# schematic.net
KiCad netlist of a schematic drawn in EAGLE
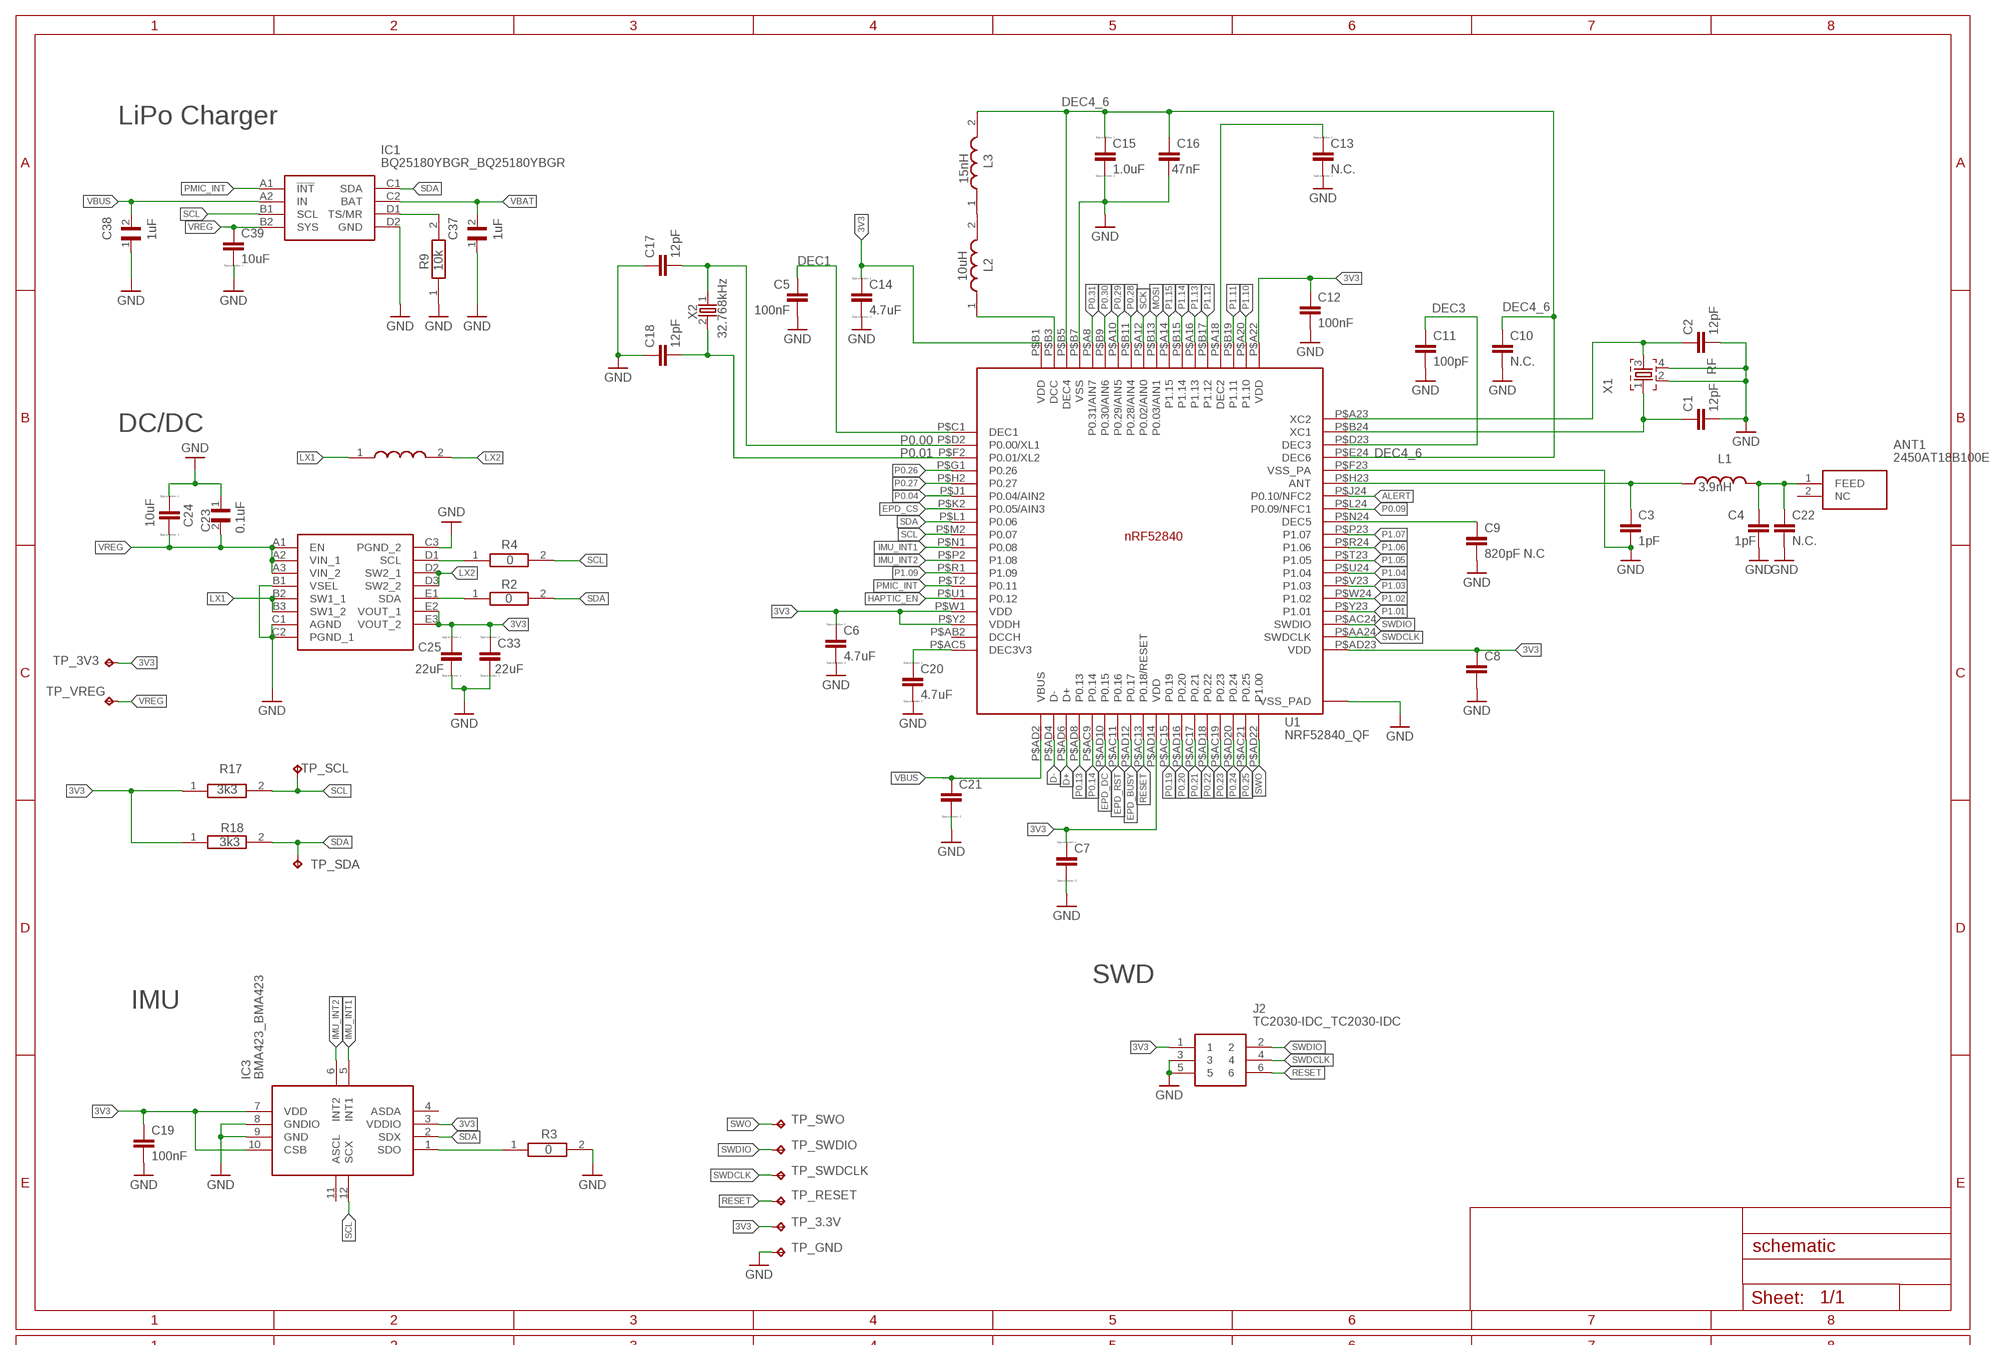
[diagram p0: schematic, sheet 1, part 1 of 2]
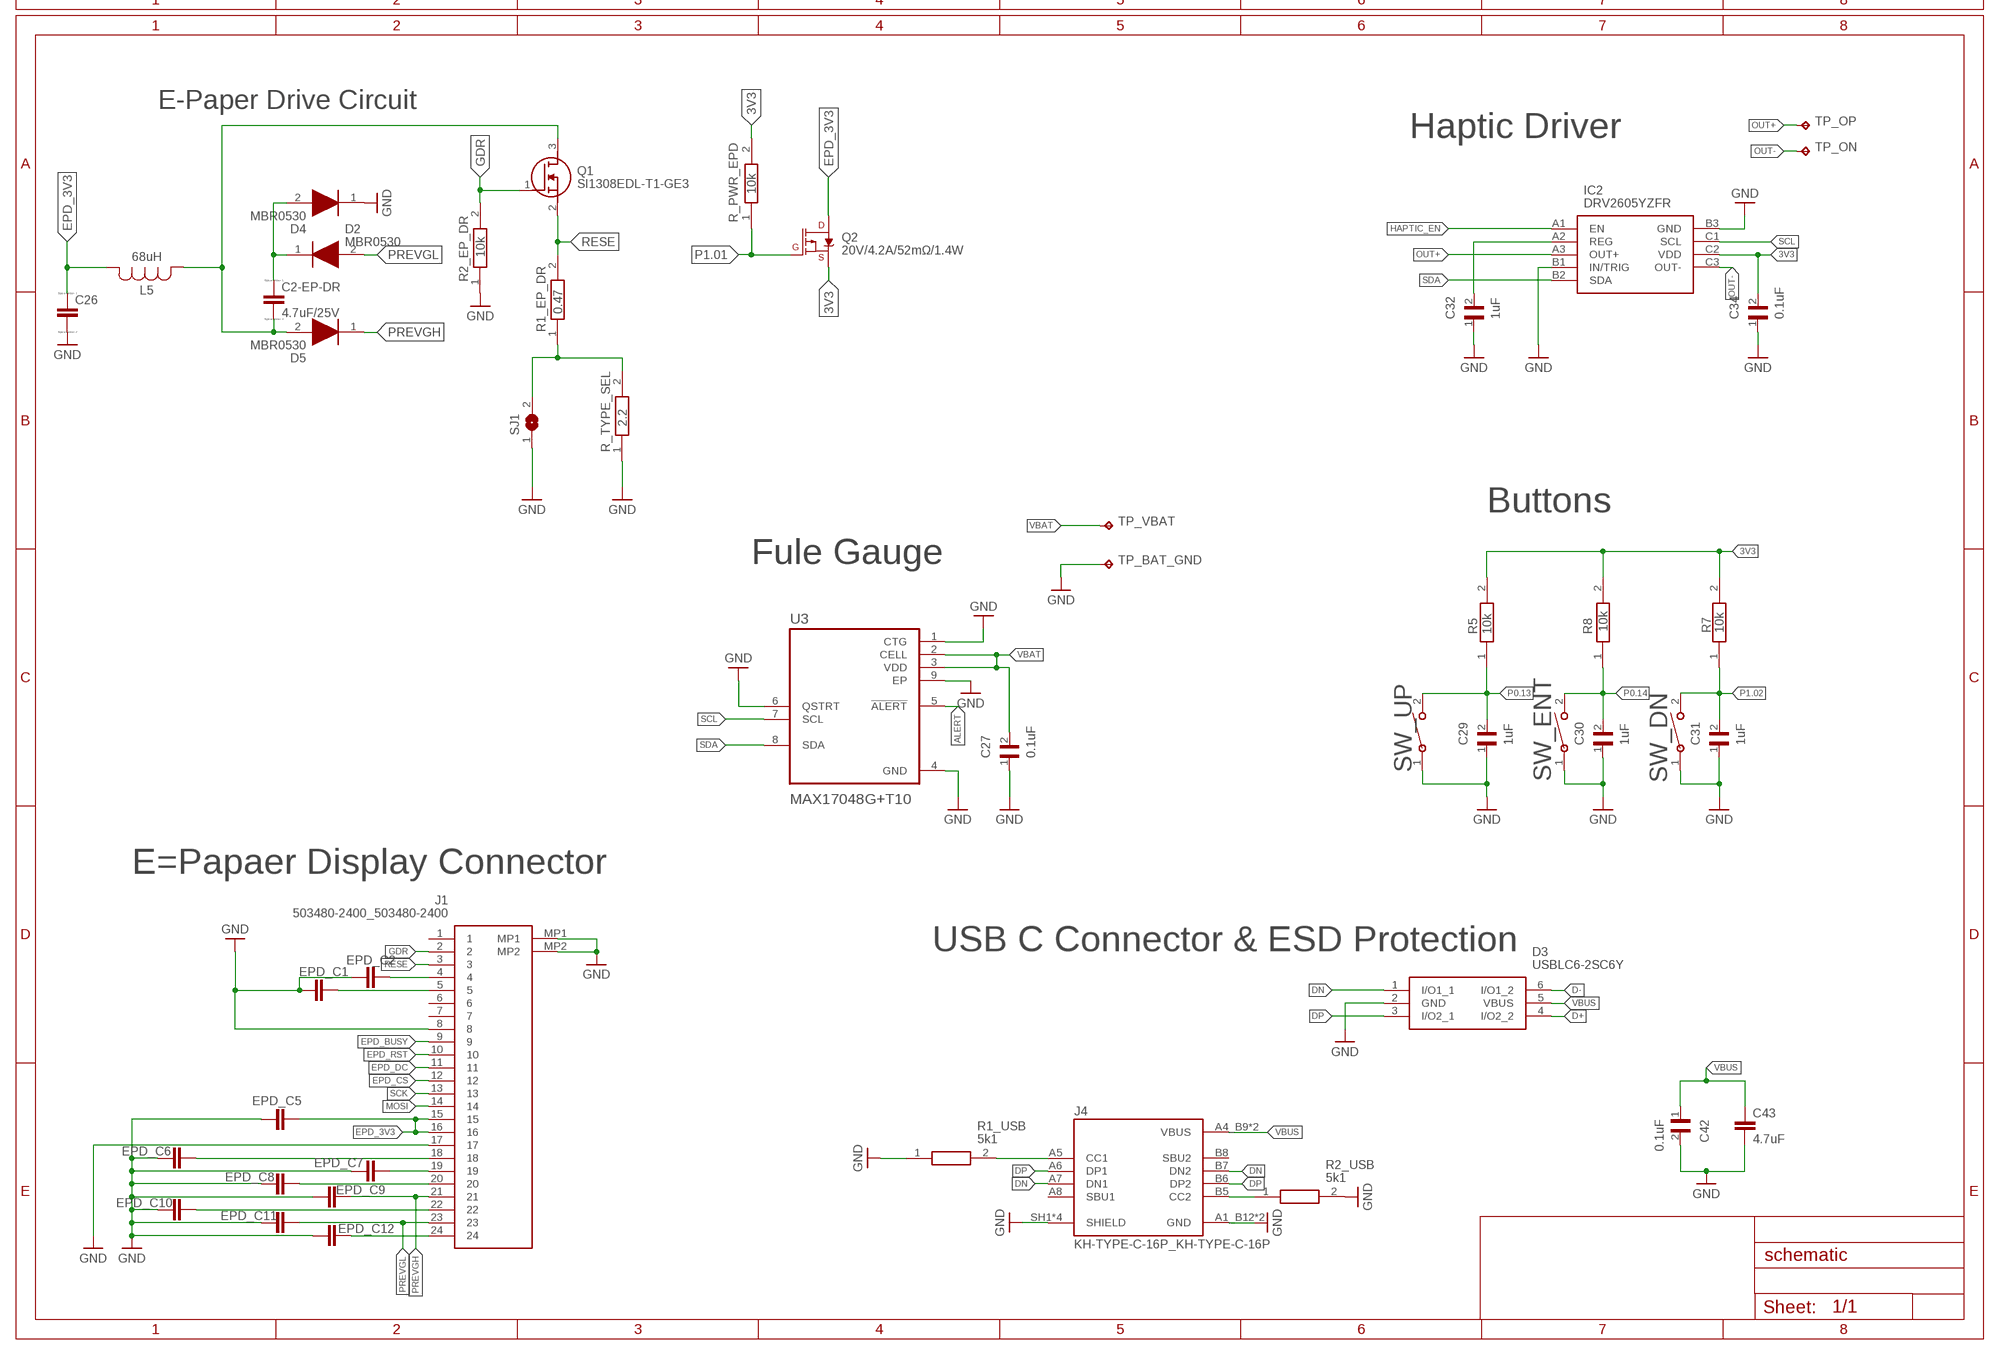
[diagram p1: schematic, sheet 1, part 2 of 2]

(export (version "E")
  (design (tool "Eeschema 10.0.6"))
  (components
    (comp (ref "ANT1")
      (value "2450AT18B100E")
      (footprint "eagle-import:2450AT18B100E_ANTC3216X140N")
      (fields (field (name "MOUSER_PART_NUMBER") "609-2450AT18B100E"))
      (libsource (lib "eagle-import") (part "2450AT18B100E_2450AT18B100E"))
    )
    (comp (ref "C1")
      (value "12pF")
      (footprint "eagle-import:NORDIC_NRF_3_RESC0201_L")
      (libsource (lib "eagle-import") (part "NORDIC_NRF_3_CAPACITOR_0201_L"))
    )
    (comp (ref "C2")
      (value "12pF")
      (footprint "eagle-import:NORDIC_NRF_3_RESC0201_L")
      (libsource (lib "eagle-import") (part "NORDIC_NRF_3_CAPACITOR_0201_L"))
    )
    (comp (ref "C2-EP-DR")
      (value "4.7uF/25V")
      (footprint "eagle-import:ESP32_C6_LIBRARY_1_ESP32_WROVER_EAGLE-LTSPICE_C0402")
      (libsource (lib "eagle-import") (part "ESP32_C6_LIBRARY_1_ESP32_WROVER_EAGLE-LTSPICE_CC0402"))
    )
    (comp (ref "C3")
      (value "1pF")
      (footprint "eagle-import:NORDIC_NRF_3_RESC0201_L")
      (libsource (lib "eagle-import") (part "NORDIC_NRF_3_CAPACITOR_0201_L"))
    )
    (comp (ref "C4")
      (value "1pF")
      (footprint "eagle-import:NORDIC_NRF_3_RESC0201_L")
      (libsource (lib "eagle-import") (part "NORDIC_NRF_3_CAPACITOR_0201_L"))
    )
    (comp (ref "C5")
      (value "100nF")
      (footprint "eagle-import:NORDIC_NRF_3_RESC0201_L")
      (libsource (lib "eagle-import") (part "NORDIC_NRF_3_CAPACITOR_0201_L"))
    )
    (comp (ref "C6")
      (value "4.7uF")
      (footprint "eagle-import:ESP32_C6_LIBRARY_1_ESP32_WROVER_EAGLE-LTSPICE_C0402")
      (libsource (lib "eagle-import") (part "ESP32_C6_LIBRARY_1_ESP32_WROVER_EAGLE-LTSPICE_CC0402"))
    )
    (comp (ref "C7")
      (value "ESP32_C6_LIBRARY_1_ESP32_WROVER_EAGLE-LTSPICE_CC0402")
      (footprint "eagle-import:ESP32_C6_LIBRARY_1_ESP32_WROVER_EAGLE-LTSPICE_C0402")
      (libsource (lib "eagle-import") (part "ESP32_C6_LIBRARY_1_ESP32_WROVER_EAGLE-LTSPICE_CC0402"))
    )
    (comp (ref "C8")
      (value "NORDIC_NRF_3_CAPACITOR_0201_L")
      (footprint "eagle-import:NORDIC_NRF_3_RESC0201_L")
      (libsource (lib "eagle-import") (part "NORDIC_NRF_3_CAPACITOR_0201_L"))
    )
    (comp (ref "C9")
      (value "820pF N.C")
      (footprint "eagle-import:NORDIC_NRF_3_RESC0201_L")
      (libsource (lib "eagle-import") (part "NORDIC_NRF_3_CAPACITOR_0201_L"))
    )
    (comp (ref "C10")
      (value "N.C.")
      (footprint "eagle-import:NORDIC_NRF_3_RESC0201_L")
      (libsource (lib "eagle-import") (part "NORDIC_NRF_3_CAPACITOR_0201_L"))
    )
    (comp (ref "C11")
      (value "100pF")
      (footprint "eagle-import:NORDIC_NRF_3_RESC0201_L")
      (libsource (lib "eagle-import") (part "NORDIC_NRF_3_CAPACITOR_0201_L"))
    )
    (comp (ref "C12")
      (value "100nF")
      (footprint "eagle-import:NORDIC_NRF_3_RESC0201_L")
      (libsource (lib "eagle-import") (part "NORDIC_NRF_3_CAPACITOR_0201_L"))
    )
    (comp (ref "C13")
      (value "N.C.")
      (footprint "eagle-import:ESP32_C6_LIBRARY_1_ESP32_WROVER_EAGLE-LTSPICE_C0402")
      (libsource (lib "eagle-import") (part "ESP32_C6_LIBRARY_1_ESP32_WROVER_EAGLE-LTSPICE_CC0402"))
    )
    (comp (ref "C14")
      (value "4.7uF")
      (footprint "eagle-import:ESP32_C6_LIBRARY_1_ESP32_WROVER_EAGLE-LTSPICE_C0402")
      (libsource (lib "eagle-import") (part "ESP32_C6_LIBRARY_1_ESP32_WROVER_EAGLE-LTSPICE_CC0402"))
    )
    (comp (ref "C15")
      (value "1.0uF")
      (footprint "eagle-import:ESP32_C6_LIBRARY_1_ESP32_WROVER_EAGLE-LTSPICE_C0402")
      (libsource (lib "eagle-import") (part "ESP32_C6_LIBRARY_1_ESP32_WROVER_EAGLE-LTSPICE_CC0402"))
    )
    (comp (ref "C16")
      (value "47nF")
      (footprint "eagle-import:NORDIC_NRF_3_RESC0201_L")
      (libsource (lib "eagle-import") (part "NORDIC_NRF_3_CAPACITOR_0201_L"))
    )
    (comp (ref "C17")
      (value "12pF")
      (footprint "eagle-import:NORDIC_NRF_3_RESC0201_L")
      (libsource (lib "eagle-import") (part "NORDIC_NRF_3_CAPACITOR_0201_L"))
    )
    (comp (ref "C18")
      (value "12pF")
      (footprint "eagle-import:NORDIC_NRF_3_RESC0201_L")
      (libsource (lib "eagle-import") (part "NORDIC_NRF_3_CAPACITOR_0201_L"))
    )
    (comp (ref "C19")
      (value "100nF")
      (footprint "eagle-import:NORDIC_NRF_3_RESC0201_L")
      (libsource (lib "eagle-import") (part "NORDIC_NRF_3_CAPACITOR_0201_L"))
    )
    (comp (ref "C20")
      (value "4.7uF")
      (footprint "eagle-import:ESP32_C6_LIBRARY_1_ESP32_WROVER_EAGLE-LTSPICE_C0402")
      (libsource (lib "eagle-import") (part "ESP32_C6_LIBRARY_1_ESP32_WROVER_EAGLE-LTSPICE_CC0402"))
    )
    (comp (ref "C21")
      (value "ESP32_C6_LIBRARY_1_ESP32_WROVER_EAGLE-LTSPICE_CC0402")
      (footprint "eagle-import:ESP32_C6_LIBRARY_1_ESP32_WROVER_EAGLE-LTSPICE_C0402")
      (libsource (lib "eagle-import") (part "ESP32_C6_LIBRARY_1_ESP32_WROVER_EAGLE-LTSPICE_CC0402"))
    )
    (comp (ref "C22")
      (value "N.C.")
      (footprint "eagle-import:NORDIC_NRF_3_RESC0201_L")
      (libsource (lib "eagle-import") (part "NORDIC_NRF_3_CAPACITOR_0201_L"))
    )
    (comp (ref "C23")
      (value "0.1uF")
      (footprint "eagle-import:GRM011R60J152KE01L_2_CAPC0201X13N")
      (fields (field (name "MF") "Murata") (field (name "MP") "GRM011R60J152KE01L"))
      (libsource (lib "eagle-import") (part "GRM011R60J152KE01L_2_GRM011R60J152KE01L"))
    )
    (comp (ref "C24")
      (value "10uF")
      (footprint "eagle-import:ESP32_C6_LIBRARY_1_ESP32_WROVER_EAGLE-LTSPICE_C0402")
      (libsource (lib "eagle-import") (part "ESP32_C6_LIBRARY_1_ESP32_WROVER_EAGLE-LTSPICE_CC0402"))
    )
    (comp (ref "C25")
      (value "22uF")
      (footprint "eagle-import:ESP32_C6_LIBRARY_1_ESP32_WROVER_EAGLE-LTSPICE_C0402")
      (libsource (lib "eagle-import") (part "ESP32_C6_LIBRARY_1_ESP32_WROVER_EAGLE-LTSPICE_CC0402"))
    )
    (comp (ref "C26")
      (value "ESP32_C6_LIBRARY_1_ESP32_WROVER_EAGLE-LTSPICE_CC0402")
      (footprint "eagle-import:ESP32_C6_LIBRARY_1_ESP32_WROVER_EAGLE-LTSPICE_C0402")
      (libsource (lib "eagle-import") (part "ESP32_C6_LIBRARY_1_ESP32_WROVER_EAGLE-LTSPICE_CC0402"))
    )
    (comp (ref "C27")
      (value "0.1uF")
      (footprint "eagle-import:GRM011R60J152KE01L_2_CAPC0201X13N")
      (fields (field (name "MF") "Murata") (field (name "MP") "GRM011R60J152KE01L"))
      (libsource (lib "eagle-import") (part "GRM011R60J152KE01L_2_GRM011R60J152KE01L"))
    )
    (comp (ref "C29")
      (value "1uF")
      (footprint "eagle-import:GRM011R60J152KE01L_2_CAPC0201X13N")
      (fields (field (name "MF") "Murata") (field (name "MP") "GRM011R60J152KE01L"))
      (libsource (lib "eagle-import") (part "GRM011R60J152KE01L_2_GRM011R60J152KE01L"))
    )
    (comp (ref "C30")
      (value "1uF")
      (footprint "eagle-import:GRM011R60J152KE01L_2_CAPC0201X13N")
      (fields (field (name "MF") "Murata") (field (name "MP") "GRM011R60J152KE01L"))
      (libsource (lib "eagle-import") (part "GRM011R60J152KE01L_2_GRM011R60J152KE01L"))
    )
    (comp (ref "C31")
      (value "1uF")
      (footprint "eagle-import:GRM011R60J152KE01L_2_CAPC0201X13N")
      (fields (field (name "MF") "Murata") (field (name "MP") "GRM011R60J152KE01L"))
      (libsource (lib "eagle-import") (part "GRM011R60J152KE01L_2_GRM011R60J152KE01L"))
    )
    (comp (ref "C32")
      (value "1uF")
      (footprint "eagle-import:GRM011R60J152KE01L_2_CAPC0201X13N")
      (fields (field (name "MF") "Murata") (field (name "MP") "GRM011R60J152KE01L"))
      (libsource (lib "eagle-import") (part "GRM011R60J152KE01L_2_GRM011R60J152KE01L"))
    )
    (comp (ref "C33")
      (value "22uF")
      (footprint "eagle-import:ESP32_C6_LIBRARY_1_ESP32_WROVER_EAGLE-LTSPICE_C0402")
      (libsource (lib "eagle-import") (part "ESP32_C6_LIBRARY_1_ESP32_WROVER_EAGLE-LTSPICE_CC0402"))
    )
    (comp (ref "C34")
      (value "0.1uF")
      (footprint "eagle-import:GRM011R60J152KE01L_2_CAPC0201X13N")
      (fields (field (name "MF") "Murata") (field (name "MP") "GRM011R60J152KE01L"))
      (libsource (lib "eagle-import") (part "GRM011R60J152KE01L_2_GRM011R60J152KE01L"))
    )
    (comp (ref "C37")
      (value "1uF")
      (footprint "eagle-import:GRM011R60J152KE01L_2_CAPC0201X13N")
      (fields (field (name "MF") "Murata") (field (name "MP") "GRM011R60J152KE01L"))
      (libsource (lib "eagle-import") (part "GRM011R60J152KE01L_2_GRM011R60J152KE01L"))
    )
    (comp (ref "C38")
      (value "1uF")
      (footprint "eagle-import:GRM011R60J152KE01L_2_CAPC0201X13N")
      (fields (field (name "MF") "Murata") (field (name "MP") "GRM011R60J152KE01L"))
      (libsource (lib "eagle-import") (part "GRM011R60J152KE01L_2_GRM011R60J152KE01L"))
    )
    (comp (ref "C39")
      (value "10uF")
      (footprint "eagle-import:ESP32_C6_LIBRARY_1_ESP32_WROVER_EAGLE-LTSPICE_C0402")
      (libsource (lib "eagle-import") (part "ESP32_C6_LIBRARY_1_ESP32_WROVER_EAGLE-LTSPICE_CC0402"))
    )
    (comp (ref "C42")
      (value "0.1uF")
      (footprint "eagle-import:GRM011R60J152KE01L_2_CAPC0201X13N")
      (fields (field (name "MF") "Murata") (field (name "MP") "GRM011R60J152KE01L"))
      (libsource (lib "eagle-import") (part "GRM011R60J152KE01L_2_GRM011R60J152KE01L"))
    )
    (comp (ref "C43")
      (value "4.7uF")
      (footprint "eagle-import:NORDIC_NRF_3_RESC0402_L")
      (libsource (lib "eagle-import") (part "NORDIC_NRF_3_CAPACITOR_0402_L"))
    )
    (comp (ref "D2")
      (value "MBR0530")
      (footprint "eagle-import:ESP32_C6_LIBRARY_5_SOD3716X135N")
      (fields (field (name "MF") "ON Semiconductor"))
      (libsource (lib "eagle-import") (part "ESP32_C6_LIBRARY_5_MBR0530"))
    )
    (comp (ref "D3")
      (value "USBLC6-2SC6Y")
      (footprint "eagle-import:ESP32_C6_LIBRARY_3_SOT95P280X145-6N")
      (fields (field (name "MF") "STMicroelectronics"))
      (libsource (lib "eagle-import") (part "ESP32_C6_LIBRARY_3_USBLC6-2SC6Y"))
    )
    (comp (ref "D4")
      (value "MBR0530")
      (footprint "eagle-import:ESP32_C6_LIBRARY_5_SOD3716X135N")
      (fields (field (name "MF") "ON Semiconductor"))
      (libsource (lib "eagle-import") (part "ESP32_C6_LIBRARY_5_MBR0530"))
    )
    (comp (ref "D5")
      (value "MBR0530")
      (footprint "eagle-import:ESP32_C6_LIBRARY_5_SOD3716X135N")
      (fields (field (name "MF") "ON Semiconductor"))
      (libsource (lib "eagle-import") (part "ESP32_C6_LIBRARY_5_MBR0530"))
    )
    (comp (ref "EPD_C1")
      (value "NORDIC_NRF_3_CAPACITOR_0402_L")
      (footprint "eagle-import:NORDIC_NRF_3_RESC0402_L")
      (libsource (lib "eagle-import") (part "NORDIC_NRF_3_CAPACITOR_0402_L"))
    )
    (comp (ref "EPD_C2")
      (value "NORDIC_NRF_3_CAPACITOR_0402_L")
      (footprint "eagle-import:NORDIC_NRF_3_RESC0402_L")
      (libsource (lib "eagle-import") (part "NORDIC_NRF_3_CAPACITOR_0402_L"))
    )
    (comp (ref "EPD_C5")
      (value "NORDIC_NRF_3_CAPACITOR_0402_L")
      (footprint "eagle-import:NORDIC_NRF_3_RESC0402_L")
      (libsource (lib "eagle-import") (part "NORDIC_NRF_3_CAPACITOR_0402_L"))
    )
    (comp (ref "EPD_C6")
      (value "NORDIC_NRF_3_CAPACITOR_0402_L")
      (footprint "eagle-import:NORDIC_NRF_3_RESC0402_L")
      (libsource (lib "eagle-import") (part "NORDIC_NRF_3_CAPACITOR_0402_L"))
    )
    (comp (ref "EPD_C7")
      (value "NORDIC_NRF_3_CAPACITOR_0402_L")
      (footprint "eagle-import:NORDIC_NRF_3_RESC0402_L")
      (libsource (lib "eagle-import") (part "NORDIC_NRF_3_CAPACITOR_0402_L"))
    )
    (comp (ref "EPD_C8")
      (value "NORDIC_NRF_3_CAPACITOR_0402_L")
      (footprint "eagle-import:NORDIC_NRF_3_RESC0402_L")
      (libsource (lib "eagle-import") (part "NORDIC_NRF_3_CAPACITOR_0402_L"))
    )
    (comp (ref "EPD_C9")
      (value "NORDIC_NRF_3_CAPACITOR_0402_L")
      (footprint "eagle-import:NORDIC_NRF_3_RESC0402_L")
      (libsource (lib "eagle-import") (part "NORDIC_NRF_3_CAPACITOR_0402_L"))
    )
    (comp (ref "EPD_C10")
      (value "NORDIC_NRF_3_CAPACITOR_0402_L")
      (footprint "eagle-import:NORDIC_NRF_3_RESC0402_L")
      (libsource (lib "eagle-import") (part "NORDIC_NRF_3_CAPACITOR_0402_L"))
    )
    (comp (ref "EPD_C11")
      (value "NORDIC_NRF_3_CAPACITOR_0402_L")
      (footprint "eagle-import:NORDIC_NRF_3_RESC0402_L")
      (libsource (lib "eagle-import") (part "NORDIC_NRF_3_CAPACITOR_0402_L"))
    )
    (comp (ref "EPD_C12")
      (value "NORDIC_NRF_3_CAPACITOR_0402_L")
      (footprint "eagle-import:NORDIC_NRF_3_RESC0402_L")
      (libsource (lib "eagle-import") (part "NORDIC_NRF_3_CAPACITOR_0402_L"))
    )
    (comp (ref "IC1")
      (value "BQ25180YBGR_BQ25180YBGR")
      (footprint "eagle-import:BQ25180YBGR_BGA8C40P2X4_100X155X50")
      (fields
        (field (name "ARROW_PART_NUMBER") "BQ25180YBGR")
        (field (name "MOUSER_PART_NUMBER") "595-BQ25180YBGR")
      )
      (libsource (lib "eagle-import") (part "BQ25180YBGR_BQ25180YBGR"))
    )
    (comp (ref "IC2")
      (value "DRV2605YZFR")
      (footprint "eagle-import:DRV2605YZFR_BGA9C50P3X3_144X144X62")
      (libsource (lib "eagle-import") (part "DRV2605YZFR_DRV2605YZFR"))
    )
    (comp (ref "IC3")
      (value "BMA423_BMA423")
      (footprint "eagle-import:BMA423_BMA423")
      (fields (field (name "ARROW_PART_NUMBER") "BMA423") (field (name "MOUSER_PART_NUMBER") "262-BMA423"))
      (libsource (lib "eagle-import") (part "BMA423_BMA423"))
    )
    (comp (ref "IC9")
      (value "RT6160AWSC_RT6160AWSC")
      (footprint "eagle-import:RT6160AWSC_BGA15C40P3X5_140X230X60")
      (fields
        (field (name "MANUFACTURER_PART_NUMBER") "RT6160AWSC")
        (field (name "MOUSER_PART_NUMBER") "835-RT6160AWSC")
      )
      (libsource (lib "eagle-import") (part "RT6160AWSC_RT6160AWSC"))
    )
    (comp (ref "J1")
      (value "503480-2400_503480-2400")
      (footprint "eagle-import:503480-2400_5034802400")
      (fields
        (field (name "MANUFACTURER_PART_NUMBER") "503480-2400")
        (field (name "MOUSER_PART_NUMBER") "538-503480-2400")
      )
      (libsource (lib "eagle-import") (part "503480-2400_503480-2400"))
    )
    (comp (ref "J2")
      (value "TC2030-IDC_TC2030-IDC")
      (footprint "eagle-import:TC2030-IDC_TC2030IDC")
      (fields (field (name "MANUFACTURER_PART_NUMBER") "TC2030-IDC"))
      (libsource (lib "eagle-import") (part "TC2030-IDC_TC2030-IDC"))
    )
    (comp (ref "J4")
      (value "KH-TYPE-C-16P_KH-TYPE-C-16P")
      (footprint "eagle-import:KH-TYPE-C-16P_KINGHELM_KH-TYPE-C-16P")
      (fields (field (name "MF") "kinghelm") (field (name "MP") "KH-TYPE-C-16P"))
      (libsource (lib "eagle-import") (part "KH-TYPE-C-16P_KH-TYPE-C-16P"))
    )
    (comp (ref "L1")
      (value "3.9nH")
      (footprint "eagle-import:NORDIC_NRF_2_RESC0805_N")
      (libsource (lib "eagle-import") (part "NORDIC_NRF_2_INDUCTOR_0805_N"))
    )
    (comp (ref "L2")
      (value "10uH")
      (footprint "eagle-import:MLP2016SR47MT0S1_INDC2016X100N")
      (fields (field (name "MANUFACTURER_PART_NUMBER") "FTC252012SR47MBCA"))
      (libsource (lib "eagle-import") (part "MLP2016SR47MT0S1_FTC252012SR47MBCA"))
    )
    (comp (ref "L3")
      (value "15nH")
      (footprint "eagle-import:MLP2016SR47MT0S1_INDC2016X100N")
      (fields (field (name "MANUFACTURER_PART_NUMBER") "FTC252012SR47MBCA"))
      (libsource (lib "eagle-import") (part "MLP2016SR47MT0S1_FTC252012SR47MBCA"))
    )
    (comp (ref "L5")
      (value "68uH")
      (footprint "eagle-import:ESP32_C6_LIBRARY_2_IND_4828-WE-TPC_WRE")
      (fields
        (field (name "MANUFACTURER_PART_NUMBER") "744043680")
        (field (name "COPYRIGHT") "Copyright (C) 2024 Ultra Librarian. All rights reserved.")
      )
      (libsource (lib "eagle-import") (part "ESP32_C6_LIBRARY_2_744043680IND_4828-WE-TPC_WRE"))
    )
    (comp (ref "L7")
      (value "MLP2016SR47MT0S1_FTC252012SR47MBCA")
      (footprint "eagle-import:MLP2016SR47MT0S1_INDC2016X100N")
      (fields (field (name "MANUFACTURER_PART_NUMBER") "FTC252012SR47MBCA"))
      (libsource (lib "eagle-import") (part "MLP2016SR47MT0S1_FTC252012SR47MBCA"))
    )
    (comp (ref "Q1")
      (value "SI1308EDL-T1-GE3")
      (footprint "eagle-import:ESP32_C6_LIBRARY_6_SOT65P210X110-3N")
      (fields (field (name "MF") "Vishay Siliconix"))
      (libsource (lib "eagle-import") (part "ESP32_C6_LIBRARY_6_SI1308EDL-T1-GE3"))
    )
    (comp (ref "Q2")
      (value "20V/4.2A/52mΩ/1.4W")
      (footprint "eagle-import:ESP32_C6_LIBRARY_4_ESP32_C6_LIBRARY_4_ESP32_C6_LIBRARY_4_ESP32_C6_LIBRARY_4_ESP32_WROVER_SPARKFUN-DISCRETESEMI_SOT23-3")
      (libsource (lib "eagle-import") (part "ESP32_C6_LIBRARY_4_ESP32_WROVER_SPARKFUN-DISCRETESEMI_MOSFET_PCH-DMG2305UX-7"))
    )
    (comp (ref "R1_EP_DR")
      (value "0.47")
      (footprint "eagle-import:CPF0201D7K68C1_0201")
      (libsource (lib "eagle-import") (part "CPF0201D7K68C1_CPF0201D7K68C1"))
    )
    (comp (ref "R1_USB")
      (value "5k1")
      (footprint "eagle-import:ERA-1AEB3401C_0201")
      (libsource (lib "eagle-import") (part "ERA-1AEB3401C_CPF0201D7K68C1"))
    )
    (comp (ref "R2")
      (value "0")
      (footprint "eagle-import:CPF0201D7K68C1_0201")
      (libsource (lib "eagle-import") (part "CPF0201D7K68C1_CPF0201D7K68C1"))
    )
    (comp (ref "R2_EP_DR")
      (value "10k")
      (footprint "eagle-import:CPF0201D7K68C1_0201")
      (libsource (lib "eagle-import") (part "CPF0201D7K68C1_CPF0201D7K68C1"))
    )
    (comp (ref "R2_USB")
      (value "5k1")
      (footprint "eagle-import:ERA-1AEB3401C_0201")
      (libsource (lib "eagle-import") (part "ERA-1AEB3401C_CPF0201D7K68C1"))
    )
    (comp (ref "R3")
      (value "0")
      (footprint "eagle-import:CPF0201D7K68C1_0201")
      (libsource (lib "eagle-import") (part "CPF0201D7K68C1_CPF0201D7K68C1"))
    )
    (comp (ref "R4")
      (value "0")
      (footprint "eagle-import:CPF0201D7K68C1_0201")
      (libsource (lib "eagle-import") (part "CPF0201D7K68C1_CPF0201D7K68C1"))
    )
    (comp (ref "R5")
      (value "10k")
      (footprint "eagle-import:ERA-1AEB3401C_0201")
      (libsource (lib "eagle-import") (part "ERA-1AEB3401C_CPF0201D7K68C1"))
    )
    (comp (ref "R7")
      (value "10k")
      (footprint "eagle-import:ERA-1AEB3401C_0201")
      (libsource (lib "eagle-import") (part "ERA-1AEB3401C_CPF0201D7K68C1"))
    )
    (comp (ref "R8")
      (value "10k")
      (footprint "eagle-import:ERA-1AEB3401C_0201")
      (libsource (lib "eagle-import") (part "ERA-1AEB3401C_CPF0201D7K68C1"))
    )
    (comp (ref "R9")
      (value "10k")
      (footprint "eagle-import:CPF0201D7K68C1_0201")
      (libsource (lib "eagle-import") (part "CPF0201D7K68C1_CPF0201D7K68C1"))
    )
    (comp (ref "R17")
      (value "3k3")
      (footprint "eagle-import:CPF0201D7K68C1_0201")
      (libsource (lib "eagle-import") (part "CPF0201D7K68C1_CPF0201D7K68C1"))
    )
    (comp (ref "R18")
      (value "3k3")
      (footprint "eagle-import:CPF0201D7K68C1_0201")
      (libsource (lib "eagle-import") (part "CPF0201D7K68C1_CPF0201D7K68C1"))
    )
    (comp (ref "R_PWR_EPD")
      (value "10k")
      (footprint "eagle-import:CPF0201D7K68C1_0201")
      (libsource (lib "eagle-import") (part "CPF0201D7K68C1_CPF0201D7K68C1"))
    )
    (comp (ref "R_TYPE_SEL")
      (value "2.2")
      (footprint "eagle-import:CPF0201D7K68C1_0201")
      (libsource (lib "eagle-import") (part "CPF0201D7K68C1_CPF0201D7K68C1"))
    )
    (comp (ref "SJ1")
      (value "ESP32_C6_LIBRARY_7_JUMPER_SJ")
      (footprint "eagle-import:ESP32_C6_LIBRARY_7_JUMPER_SJ")
      (libsource (lib "eagle-import") (part "ESP32_C6_LIBRARY_7_JUMPER_SJ"))
    )
    (comp (ref "SW_DN")
      (value "2025-10-22_07-23-44_LIBRARY_EVP-AKE31ASW_EVP-AKE31A_PAN")
      (footprint "eagle-import:2025-10-22_07-23-44_LIBRARY_SW_EVP-AKE31A_PAN")
      (fields
        (field (name "MANUFACTURER_PART_NUMBER") "EVP-AKE31A")
        (field (name "COPYRIGHT") "Copyright (C) 2025 Ultra Librarian. All rights reserved.")
      )
      (libsource (lib "eagle-import") (part "2025-10-22_07-23-44_LIBRARY_EVP-AKE31ASW_EVP-AKE31A_PAN"))
    )
    (comp (ref "SW_ENT")
      (value "2025-10-22_07-23-44_LIBRARY_EVP-AKE31ASW_EVP-AKE31A_PAN")
      (footprint "eagle-import:2025-10-22_07-23-44_LIBRARY_SW_EVP-AKE31A_PAN")
      (fields
        (field (name "MANUFACTURER_PART_NUMBER") "EVP-AKE31A")
        (field (name "COPYRIGHT") "Copyright (C) 2025 Ultra Librarian. All rights reserved.")
      )
      (libsource (lib "eagle-import") (part "2025-10-22_07-23-44_LIBRARY_EVP-AKE31ASW_EVP-AKE31A_PAN"))
    )
    (comp (ref "SW_UP")
      (value "2025-10-22_07-23-44_LIBRARY_EVP-AKE31ASW_EVP-AKE31A_PAN")
      (footprint "eagle-import:2025-10-22_07-23-44_LIBRARY_SW_EVP-AKE31A_PAN")
      (fields
        (field (name "MANUFACTURER_PART_NUMBER") "EVP-AKE31A")
        (field (name "COPYRIGHT") "Copyright (C) 2025 Ultra Librarian. All rights reserved.")
      )
      (libsource (lib "eagle-import") (part "2025-10-22_07-23-44_LIBRARY_EVP-AKE31ASW_EVP-AKE31A_PAN"))
    )
    (comp (ref "TP_3.3V")
      (value "HECTOR_WATCH_1_TPTP20R")
      (footprint "eagle-import:HECTOR_WATCH_1_TP20R")
      (libsource (lib "eagle-import") (part "HECTOR_WATCH_1_TPTP20R"))
    )
    (comp (ref "TP_3V3")
      (value "TP_3V3")
      (footprint "eagle-import:HECTOR_WATCH_1_TP20R")
      (libsource (lib "eagle-import") (part "HECTOR_WATCH_1_TPTP20R"))
    )
    (comp (ref "TP_BAT_GND")
      (value "HECTOR_WATCH_1_TPTP20R")
      (footprint "eagle-import:HECTOR_WATCH_1_TP20R")
      (libsource (lib "eagle-import") (part "HECTOR_WATCH_1_TPTP20R"))
    )
    (comp (ref "TP_GND")
      (value "HECTOR_WATCH_1_TPTP20R")
      (footprint "eagle-import:HECTOR_WATCH_1_TP20R")
      (libsource (lib "eagle-import") (part "HECTOR_WATCH_1_TPTP20R"))
    )
    (comp (ref "TP_ON")
      (value "HECTOR_WATCH_1_TPTP20R")
      (footprint "eagle-import:HECTOR_WATCH_1_TP20R")
      (libsource (lib "eagle-import") (part "HECTOR_WATCH_1_TPTP20R"))
    )
    (comp (ref "TP_OP")
      (value "HECTOR_WATCH_1_TPTP20R")
      (footprint "eagle-import:HECTOR_WATCH_1_TP20R")
      (libsource (lib "eagle-import") (part "HECTOR_WATCH_1_TPTP20R"))
    )
    (comp (ref "TP_RESET")
      (value "HECTOR_WATCH_1_TPTP20R")
      (footprint "eagle-import:HECTOR_WATCH_1_TP20R")
      (libsource (lib "eagle-import") (part "HECTOR_WATCH_1_TPTP20R"))
    )
    (comp (ref "TP_SCL")
      (value "HECTOR_WATCH_1_TPTP20R")
      (footprint "eagle-import:HECTOR_WATCH_1_TP20R")
      (libsource (lib "eagle-import") (part "HECTOR_WATCH_1_TPTP20R"))
    )
    (comp (ref "TP_SDA")
      (value "HECTOR_WATCH_1_TPTP20R")
      (footprint "eagle-import:HECTOR_WATCH_1_TP20R")
      (libsource (lib "eagle-import") (part "HECTOR_WATCH_1_TPTP20R"))
    )
    (comp (ref "TP_SWDCLK")
      (value "HECTOR_WATCH_1_TPTP20R")
      (footprint "eagle-import:HECTOR_WATCH_1_TP20R")
      (libsource (lib "eagle-import") (part "HECTOR_WATCH_1_TPTP20R"))
    )
    (comp (ref "TP_SWDIO")
      (value "HECTOR_WATCH_1_TPTP20R")
      (footprint "eagle-import:HECTOR_WATCH_1_TP20R")
      (libsource (lib "eagle-import") (part "HECTOR_WATCH_1_TPTP20R"))
    )
    (comp (ref "TP_SWO")
      (value "HECTOR_WATCH_1_TPTP20R")
      (footprint "eagle-import:HECTOR_WATCH_1_TP20R")
      (libsource (lib "eagle-import") (part "HECTOR_WATCH_1_TPTP20R"))
    )
    (comp (ref "TP_VBAT")
      (value "HECTOR_WATCH_1_TPTP20R")
      (footprint "eagle-import:HECTOR_WATCH_1_TP20R")
      (libsource (lib "eagle-import") (part "HECTOR_WATCH_1_TPTP20R"))
    )
    (comp (ref "TP_VREG")
      (value "HECTOR_WATCH_1_TPTP20R")
      (footprint "eagle-import:HECTOR_WATCH_1_TP20R")
      (libsource (lib "eagle-import") (part "HECTOR_WATCH_1_TPTP20R"))
    )
    (comp (ref "U1")
      (value "NRF52840_QF")
      (footprint "eagle-import:NORDIC_NRF_4_AQFN50P700X700X85_HS-74N")
      (libsource (lib "eagle-import") (part "NORDIC_NRF_4_NRF52840_QF"))
    )
    (comp (ref "U3")
      (value "MAX17048G+T10")
      (footprint "eagle-import:ESP32_C6_LIBRARY_SON50P200X200X80-9N")
      (fields (field (name "MF") "Analog Devices"))
      (libsource (lib "eagle-import") (part "ESP32_C6_LIBRARY_MAX17048G+T10"))
    )
    (comp (ref "X1")
      (value "NORDIC_NRF_XTAL_32MHZ")
      (footprint "eagle-import:NORDIC_NRF_BT-XTAL_2016_N")
      (libsource (lib "eagle-import") (part "NORDIC_NRF_XTAL_32MHZ"))
    )
    (comp (ref "X2")
      (value "32.768kHz")
      (footprint "eagle-import:NORDIC_NRF_1_XTAL_3215_N")
      (libsource (lib "eagle-import") (part "NORDIC_NRF_1_XTAL_32KHZ"))
    )
  )
  (nets
    (net (code "1") (name "/DEC1") (class "Default")
      (node (ref "C5") (pin "2") (pinfunction "2_2") (pintype "passive"))
      (node (ref "U1") (pin "P$C1") (pinfunction "DEC1_P$C1") (pintype "power_in"))
    )
    (net (code "2") (name "/DEC3") (class "Default")
      (node (ref "C11") (pin "1") (pinfunction "1_1") (pintype "passive"))
      (node (ref "U1") (pin "P$D23") (pinfunction "DEC3_P$D23") (pintype "bidirectional"))
    )
    (net (code "3") (name "/DEC4_6") (class "Default")
      (node (ref "C10") (pin "1") (pinfunction "1_1") (pintype "passive"))
      (node (ref "C15") (pin "1") (pinfunction "1_1") (pintype "passive"))
      (node (ref "C16") (pin "2") (pinfunction "2_2") (pintype "passive"))
      (node (ref "L3") (pin "2") (pinfunction "2_2") (pintype "bidirectional"))
      (node (ref "U1") (pin "P$B5") (pinfunction "DEC4_P$B5") (pintype "power_in"))
      (node (ref "U1") (pin "P$E24") (pinfunction "DEC6_P$E24") (pintype "bidirectional"))
    )
    (net (code "4") (name "/P0.00") (class "Default")
      (node (ref "C17") (pin "2") (pinfunction "2_2") (pintype "passive"))
      (node (ref "U1") (pin "P$D2") (pinfunction "P0.00/XL1_P$D2") (pintype "bidirectional"))
      (node (ref "X2") (pin "1") (pinfunction "1_1") (pintype "passive"))
    )
    (net (code "5") (name "/P0.01") (class "Default")
      (node (ref "C18") (pin "2") (pinfunction "2_2") (pintype "passive"))
      (node (ref "U1") (pin "P$F2") (pinfunction "P0.01/XL2_P$F2") (pintype "bidirectional"))
      (node (ref "X2") (pin "2") (pinfunction "2_2") (pintype "passive"))
    )
    (net (code "6") (name "/RF") (class "Default")
      (node (ref "ANT1") (pin "1") (pinfunction "FEED_1") (pintype "input"))
      (node (ref "C22") (pin "1") (pinfunction "1_1") (pintype "passive"))
      (node (ref "C4") (pin "1") (pinfunction "1_1") (pintype "passive"))
      (node (ref "L1") (pin "2") (pinfunction "2_2") (pintype "passive"))
    )
    (net (code "7") (name "3V3") (class "Default")
      (node (ref "C12") (pin "1") (pinfunction "1_1") (pintype "passive"))
      (node (ref "C14") (pin "1") (pinfunction "1_1") (pintype "passive"))
      (node (ref "C19") (pin "1") (pinfunction "1_1") (pintype "passive"))
      (node (ref "C25") (pin "1") (pinfunction "1_1") (pintype "passive"))
      (node (ref "C33") (pin "1") (pinfunction "1_1") (pintype "passive"))
      (node (ref "C34") (pin "2") (pinfunction "2_2") (pintype "passive"))
      (node (ref "C6") (pin "1") (pinfunction "1_1") (pintype "passive"))
      (node (ref "C7") (pin "1") (pinfunction "1_1") (pintype "passive"))
      (node (ref "C8") (pin "1") (pinfunction "1_1") (pintype "passive"))
      (node (ref "IC2") (pin "C2") (pinfunction "VDD_C2") (pintype "bidirectional"))
      (node (ref "IC3") (pin "10") (pinfunction "CSB_10") (pintype "bidirectional"))
      (node (ref "IC3") (pin "3") (pinfunction "VDDIO_3") (pintype "bidirectional"))
      (node (ref "IC3") (pin "7") (pinfunction "VDD_7") (pintype "bidirectional"))
      (node (ref "IC9") (pin "E2") (pinfunction "VOUT_1_E2") (pintype "bidirectional"))
      (node (ref "IC9") (pin "E3") (pinfunction "VOUT_2_E3") (pintype "bidirectional"))
      (node (ref "J2") (pin "1") (pinfunction "1_1") (pintype "bidirectional"))
      (node (ref "Q2") (pin "2") (pinfunction "S_2") (pintype "bidirectional"))
      (node (ref "R17") (pin "1") (pinfunction "1_1") (pintype "bidirectional"))
      (node (ref "R18") (pin "1") (pinfunction "1_1") (pintype "bidirectional"))
      (node (ref "R5") (pin "2") (pinfunction "2_2") (pintype "bidirectional"))
      (node (ref "R7") (pin "2") (pinfunction "2_2") (pintype "bidirectional"))
      (node (ref "R8") (pin "2") (pinfunction "2_2") (pintype "bidirectional"))
      (node (ref "R_PWR_EPD") (pin "2") (pinfunction "2_2") (pintype "bidirectional"))
      (node (ref "TP_3.3V") (pin "TP") (pinfunction "TP_TP") (pintype "input"))
      (node (ref "TP_3V3") (pin "TP") (pinfunction "TP_TP") (pintype "input"))
      (node (ref "U1") (pin "P$A22") (pinfunction "VDD_P$A22") (pintype "power_in"))
      (node (ref "U1") (pin "P$AD14") (pinfunction "VDD_P$AD14") (pintype "power_in"))
      (node (ref "U1") (pin "P$AD23") (pinfunction "VDD_P$AD23") (pintype "power_in"))
      (node (ref "U1") (pin "P$B1") (pinfunction "VDD_P$B1") (pintype "power_in"))
      (node (ref "U1") (pin "P$W1") (pinfunction "VDD_P$W1") (pintype "power_in"))
      (node (ref "U1") (pin "P$Y2") (pinfunction "VDDH_P$Y2") (pintype "power_in"))
    )
    (net (code "8") (name "ALERT") (class "Default")
      (node (ref "U1") (pin "P$J24") (pinfunction "P0.10/NFC2_P$J24") (pintype "bidirectional"))
      (node (ref "U3") (pin "5") (pinfunction "~{ALERT}_5") (pintype "output"))
    )
    (net (code "9") (name "D+") (class "Default")
      (node (ref "D3") (pin "4") (pinfunction "I/O2_2_4") (pintype "bidirectional"))
      (node (ref "U1") (pin "P$AD6") (pinfunction "D+_P$AD6") (pintype "bidirectional"))
    )
    (net (code "10") (name "D-") (class "Default")
      (node (ref "D3") (pin "6") (pinfunction "I/O1_2_6") (pintype "bidirectional"))
      (node (ref "U1") (pin "P$AD4") (pinfunction "D-_P$AD4") (pintype "bidirectional"))
    )
    (net (code "11") (name "DN") (class "Default")
      (node (ref "D3") (pin "1") (pinfunction "I/O1_1_1") (pintype "bidirectional"))
      (node (ref "J4") (pin "A7") (pinfunction "DN1_A7") (pintype "bidirectional"))
      (node (ref "J4") (pin "B7") (pinfunction "DN2_B7") (pintype "bidirectional"))
    )
    (net (code "12") (name "DP") (class "Default")
      (node (ref "D3") (pin "3") (pinfunction "I/O2_1_3") (pintype "bidirectional"))
      (node (ref "J4") (pin "A6") (pinfunction "DP1_A6") (pintype "bidirectional"))
      (node (ref "J4") (pin "B6") (pinfunction "DP2_B6") (pintype "bidirectional"))
    )
    (net (code "13") (name "EPD_3V3") (class "Default")
      (node (ref "C26") (pin "1") (pinfunction "1_1") (pintype "passive"))
      (node (ref "EPD_C5") (pin "2") (pinfunction "2_2") (pintype "passive"))
      (node (ref "J1") (pin "15") (pinfunction "15_15") (pintype "bidirectional"))
      (node (ref "J1") (pin "16") (pinfunction "16_16") (pintype "bidirectional"))
      (node (ref "L5") (pin "1") (pinfunction "1_1") (pintype "passive"))
      (node (ref "Q2") (pin "3") (pinfunction "D_3") (pintype "bidirectional"))
    )
    (net (code "14") (name "EPD_BUSY") (class "Default")
      (node (ref "J1") (pin "9") (pinfunction "9_9") (pintype "bidirectional"))
      (node (ref "U1") (pin "P$AD12") (pinfunction "P0.17_P$AD12") (pintype "bidirectional"))
    )
    (net (code "15") (name "EPD_CS") (class "Default")
      (node (ref "J1") (pin "12") (pinfunction "12_12") (pintype "bidirectional"))
      (node (ref "U1") (pin "P$K2") (pinfunction "P0.05/AIN3_P$K2") (pintype "bidirectional"))
    )
    (net (code "16") (name "EPD_DC") (class "Default")
      (node (ref "J1") (pin "11") (pinfunction "11_11") (pintype "bidirectional"))
      (node (ref "U1") (pin "P$AD10") (pinfunction "P0.15_P$AD10") (pintype "bidirectional"))
    )
    (net (code "17") (name "EPD_RST") (class "Default")
      (node (ref "J1") (pin "10") (pinfunction "10_10") (pintype "bidirectional"))
      (node (ref "U1") (pin "P$AC11") (pinfunction "P0.16_P$AC11") (pintype "bidirectional"))
    )
    (net (code "18") (name "GDR") (class "Default")
      (node (ref "J1") (pin "2") (pinfunction "2_2") (pintype "bidirectional"))
      (node (ref "Q1") (pin "1") (pinfunction "G_1") (pintype "bidirectional"))
      (node (ref "R2_EP_DR") (pin "2") (pinfunction "2_2") (pintype "bidirectional"))
    )
    (net (code "19") (name "GND") (class "Default")
      (node (ref "C1") (pin "2") (pinfunction "2_2") (pintype "passive"))
      (node (ref "C10") (pin "2") (pinfunction "2_2") (pintype "passive"))
      (node (ref "C11") (pin "2") (pinfunction "2_2") (pintype "passive"))
      (node (ref "C12") (pin "2") (pinfunction "2_2") (pintype "passive"))
      (node (ref "C13") (pin "2") (pinfunction "2_2") (pintype "passive"))
      (node (ref "C14") (pin "2") (pinfunction "2_2") (pintype "passive"))
      (node (ref "C15") (pin "2") (pinfunction "2_2") (pintype "passive"))
      (node (ref "C16") (pin "1") (pinfunction "1_1") (pintype "passive"))
      (node (ref "C17") (pin "1") (pinfunction "1_1") (pintype "passive"))
      (node (ref "C18") (pin "1") (pinfunction "1_1") (pintype "passive"))
      (node (ref "C19") (pin "2") (pinfunction "2_2") (pintype "passive"))
      (node (ref "C2") (pin "2") (pinfunction "2_2") (pintype "passive"))
      (node (ref "C20") (pin "2") (pinfunction "2_2") (pintype "passive"))
      (node (ref "C21") (pin "2") (pinfunction "2_2") (pintype "passive"))
      (node (ref "C22") (pin "2") (pinfunction "2_2") (pintype "passive"))
      (node (ref "C23") (pin "1") (pinfunction "1_1") (pintype "passive"))
      (node (ref "C24") (pin "1") (pinfunction "1_1") (pintype "passive"))
      (node (ref "C25") (pin "2") (pinfunction "2_2") (pintype "passive"))
      (node (ref "C26") (pin "2") (pinfunction "2_2") (pintype "passive"))
      (node (ref "C27") (pin "1") (pinfunction "1_1") (pintype "passive"))
      (node (ref "C29") (pin "1") (pinfunction "1_1") (pintype "passive"))
      (node (ref "C3") (pin "2") (pinfunction "2_2") (pintype "passive"))
      (node (ref "C30") (pin "1") (pinfunction "1_1") (pintype "passive"))
      (node (ref "C31") (pin "1") (pinfunction "1_1") (pintype "passive"))
      (node (ref "C32") (pin "1") (pinfunction "1_1") (pintype "passive"))
      (node (ref "C33") (pin "2") (pinfunction "2_2") (pintype "passive"))
      (node (ref "C34") (pin "1") (pinfunction "1_1") (pintype "passive"))
      (node (ref "C37") (pin "1") (pinfunction "1_1") (pintype "passive"))
      (node (ref "C38") (pin "1") (pinfunction "1_1") (pintype "passive"))
      (node (ref "C39") (pin "2") (pinfunction "2_2") (pintype "passive"))
      (node (ref "C4") (pin "2") (pinfunction "2_2") (pintype "passive"))
      (node (ref "C42") (pin "2") (pinfunction "2_2") (pintype "passive"))
      (node (ref "C43") (pin "2") (pinfunction "2_2") (pintype "passive"))
      (node (ref "C5") (pin "1") (pinfunction "1_1") (pintype "passive"))
      (node (ref "C6") (pin "2") (pinfunction "2_2") (pintype "passive"))
      (node (ref "C7") (pin "2") (pinfunction "2_2") (pintype "passive"))
      (node (ref "C8") (pin "2") (pinfunction "2_2") (pintype "passive"))
      (node (ref "C9") (pin "2") (pinfunction "2_2") (pintype "passive"))
      (node (ref "D3") (pin "2") (pinfunction "GND_2") (pintype "bidirectional"))
      (node (ref "D4") (pin "1") (pinfunction "K_1") (pintype "bidirectional"))
      (node (ref "EPD_C1") (pin "1") (pinfunction "1_1") (pintype "passive"))
      (node (ref "EPD_C10") (pin "1") (pinfunction "1_1") (pintype "passive"))
      (node (ref "EPD_C11") (pin "1") (pinfunction "1_1") (pintype "passive"))
      (node (ref "EPD_C12") (pin "1") (pinfunction "1_1") (pintype "passive"))
      (node (ref "EPD_C2") (pin "1") (pinfunction "1_1") (pintype "passive"))
      (node (ref "EPD_C5") (pin "1") (pinfunction "1_1") (pintype "passive"))
      (node (ref "EPD_C6") (pin "1") (pinfunction "1_1") (pintype "passive"))
      (node (ref "EPD_C7") (pin "1") (pinfunction "1_1") (pintype "passive"))
      (node (ref "EPD_C8") (pin "1") (pinfunction "1_1") (pintype "passive"))
      (node (ref "EPD_C9") (pin "1") (pinfunction "1_1") (pintype "passive"))
      (node (ref "IC1") (pin "D2") (pinfunction "GND_D2") (pintype "bidirectional"))
      (node (ref "IC2") (pin "B1") (pinfunction "IN/TRIG_B1") (pintype "bidirectional"))
      (node (ref "IC2") (pin "B3") (pinfunction "GND_B3") (pintype "bidirectional"))
      (node (ref "IC3") (pin "8") (pinfunction "GNDIO_8") (pintype "bidirectional"))
      (node (ref "IC3") (pin "9") (pinfunction "GND_9") (pintype "bidirectional"))
      (node (ref "IC9") (pin "B1") (pinfunction "VSEL_B1") (pintype "bidirectional"))
      (node (ref "IC9") (pin "C1") (pinfunction "AGND_C1") (pintype "bidirectional"))
      (node (ref "IC9") (pin "C2") (pinfunction "PGND_1_C2") (pintype "bidirectional"))
      (node (ref "IC9") (pin "C3") (pinfunction "PGND_2_C3") (pintype "bidirectional"))
      (node (ref "J1") (pin "17") (pinfunction "17_17") (pintype "bidirectional"))
      (node (ref "J1") (pin "8") (pinfunction "8_8") (pintype "bidirectional"))
      (node (ref "J1") (pin "MP1") (pinfunction "MP1_MP1") (pintype "bidirectional"))
      (node (ref "J1") (pin "MP2") (pinfunction "MP2_MP2") (pintype "bidirectional"))
      (node (ref "J2") (pin "3") (pinfunction "3_3") (pintype "bidirectional"))
      (node (ref "J2") (pin "5") (pinfunction "5_5") (pintype "bidirectional"))
      (node (ref "J4") (pin "A12_B1") (pinfunction "GND_A12_B1") (pintype "power_in"))
      (node (ref "J4") (pin "A1_B12") (pinfunction "GND_A1_B12") (pintype "power_in"))
      (node (ref "J4") (pin "SH1") (pinfunction "SHIELD_SH1") (pintype "passive"))
      (node (ref "J4") (pin "SH2") (pinfunction "SHIELD_SH2") (pintype "passive"))
      (node (ref "J4") (pin "SH3") (pinfunction "SHIELD_SH3") (pintype "passive"))
      (node (ref "J4") (pin "SH4") (pinfunction "SHIELD_SH4") (pintype "passive"))
      (node (ref "R1_USB") (pin "1") (pinfunction "1_1") (pintype "bidirectional"))
      (node (ref "R2_EP_DR") (pin "1") (pinfunction "1_1") (pintype "bidirectional"))
      (node (ref "R2_USB") (pin "2") (pinfunction "2_2") (pintype "bidirectional"))
      (node (ref "R3") (pin "2") (pinfunction "2_2") (pintype "bidirectional"))
      (node (ref "R9") (pin "1") (pinfunction "1_1") (pintype "bidirectional"))
      (node (ref "R_TYPE_SEL") (pin "1") (pinfunction "1_1") (pintype "bidirectional"))
      (node (ref "SJ1") (pin "1") (pinfunction "1_1") (pintype "passive"))
      (node (ref "SW_DN") (pin "1") (pinfunction "1_1") (pintype "passive"))
      (node (ref "SW_ENT") (pin "1") (pinfunction "1_1") (pintype "passive"))
      (node (ref "SW_UP") (pin "1") (pinfunction "1_1") (pintype "passive"))
      (node (ref "TP_BAT_GND") (pin "TP") (pinfunction "TP_TP") (pintype "input"))
      (node (ref "TP_GND") (pin "TP") (pinfunction "TP_TP") (pintype "input"))
      (node (ref "U1") (pin "P$74") (pinfunction "VSS_PAD_P$74") (pintype "bidirectional"))
      (node (ref "U1") (pin "P$75") (pinfunction "VSS_PAD_P$75") (pintype "bidirectional"))
      (node (ref "U1") (pin "P$76") (pinfunction "VSS_PAD_P$76") (pintype "bidirectional"))
      (node (ref "U1") (pin "P$77") (pinfunction "VSS_PAD_P$77") (pintype "bidirectional"))
      (node (ref "U1") (pin "P$78") (pinfunction "VSS_PAD_P$78") (pintype "bidirectional"))
      (node (ref "U1") (pin "P$79") (pinfunction "VSS_PAD_P$79") (pintype "bidirectional"))
      (node (ref "U1") (pin "P$80") (pinfunction "VSS_PAD_P$80") (pintype "bidirectional"))
      (node (ref "U1") (pin "P$81") (pinfunction "VSS_PAD_P$81") (pintype "bidirectional"))
      (node (ref "U1") (pin "P$82") (pinfunction "VSS_PAD_P$82") (pintype "bidirectional"))
      (node (ref "U1") (pin "P$83") (pinfunction "VSS_PAD_P$83") (pintype "bidirectional"))
      (node (ref "U1") (pin "P$84") (pinfunction "VSS_PAD_P$84") (pintype "bidirectional"))
      (node (ref "U1") (pin "P$85") (pinfunction "VSS_PAD_P$85") (pintype "bidirectional"))
      (node (ref "U1") (pin "P$86") (pinfunction "VSS_PAD_P$86") (pintype "bidirectional"))
      (node (ref "U1") (pin "P$87") (pinfunction "VSS_PAD_P$87") (pintype "bidirectional"))
      (node (ref "U1") (pin "P$88") (pinfunction "VSS_PAD_P$88") (pintype "bidirectional"))
      (node (ref "U1") (pin "P$89") (pinfunction "VSS_PAD_P$89") (pintype "bidirectional"))
      (node (ref "U1") (pin "P$90") (pinfunction "VSS_PAD_P$90") (pintype "bidirectional"))
      (node (ref "U1") (pin "P$B7") (pinfunction "VSS_P$B7") (pintype "power_in"))
      (node (ref "U1") (pin "P$F23") (pinfunction "VSS_PA_P$F23") (pintype "bidirectional"))
      (node (ref "U3") (pin "1") (pinfunction "CTG_1") (pintype "power_in"))
      (node (ref "U3") (pin "4") (pinfunction "GND_4") (pintype "power_in"))
      (node (ref "U3") (pin "6") (pinfunction "QSTRT_6") (pintype "input"))
      (node (ref "U3") (pin "9") (pinfunction "EP_9") (pintype "power_in"))
      (node (ref "X1") (pin "2") (pinfunction "2_2") (pintype "passive"))
      (node (ref "X1") (pin "4") (pinfunction "4_4") (pintype "passive"))
    )
    (net (code "20") (name "HAPTIC_EN") (class "Default")
      (node (ref "IC2") (pin "A1") (pinfunction "EN_A1") (pintype "bidirectional"))
      (node (ref "U1") (pin "P$U1") (pinfunction "P0.12_P$U1") (pintype "bidirectional"))
    )
    (net (code "21") (name "IMU_INT1") (class "Default")
      (node (ref "IC3") (pin "5") (pinfunction "INT1_5") (pintype "bidirectional"))
      (node (ref "U1") (pin "P$N1") (pinfunction "P0.08_P$N1") (pintype "bidirectional"))
    )
    (net (code "22") (name "IMU_INT2") (class "Default")
      (node (ref "IC3") (pin "6") (pinfunction "INT2_6") (pintype "bidirectional"))
      (node (ref "U1") (pin "P$P2") (pinfunction "P1.08_P$P2") (pintype "bidirectional"))
    )
    (net (code "23") (name "LX1") (class "Default")
      (node (ref "IC9") (pin "B2") (pinfunction "SW1_1_B2") (pintype "bidirectional"))
      (node (ref "IC9") (pin "B3") (pinfunction "SW1_2_B3") (pintype "bidirectional"))
      (node (ref "L7") (pin "1") (pinfunction "1_1") (pintype "bidirectional"))
    )
    (net (code "24") (name "LX2") (class "Default")
      (node (ref "IC9") (pin "D2") (pinfunction "SW2_1_D2") (pintype "bidirectional"))
      (node (ref "IC9") (pin "D3") (pinfunction "SW2_2_D3") (pintype "bidirectional"))
      (node (ref "L7") (pin "2") (pinfunction "2_2") (pintype "bidirectional"))
    )
    (net (code "25") (name "MOSI") (class "Default")
      (node (ref "J1") (pin "14") (pinfunction "14_14") (pintype "bidirectional"))
      (node (ref "U1") (pin "P$B13") (pinfunction "P0.03/AIN1_P$B13") (pintype "bidirectional"))
    )
    (net (code "26") (name "Net-(D2-K)") (class "Default")
      (node (ref "C2-EP-DR") (pin "1") (pinfunction "1_1") (pintype "passive"))
      (node (ref "D2") (pin "1") (pinfunction "K_1") (pintype "bidirectional"))
      (node (ref "D4") (pin "2") (pinfunction "A_2") (pintype "bidirectional"))
    )
    (net (code "27") (name "Net-(D5-A)") (class "Default")
      (node (ref "C2-EP-DR") (pin "2") (pinfunction "2_2") (pintype "passive"))
      (node (ref "D5") (pin "2") (pinfunction "A_2") (pintype "bidirectional"))
      (node (ref "L5") (pin "2") (pinfunction "2_2") (pintype "passive"))
      (node (ref "Q1") (pin "3") (pinfunction "D_3") (pintype "bidirectional"))
    )
    (net (code "28") (name "Net-(EPD_C1-Pad2)") (class "Default")
      (node (ref "EPD_C1") (pin "2") (pinfunction "2_2") (pintype "passive"))
      (node (ref "J1") (pin "5") (pinfunction "5_5") (pintype "bidirectional"))
    )
    (net (code "29") (name "Net-(EPD_C2-Pad2)") (class "Default")
      (node (ref "EPD_C2") (pin "2") (pinfunction "2_2") (pintype "passive"))
      (node (ref "J1") (pin "4") (pinfunction "4_4") (pintype "bidirectional"))
    )
    (net (code "30") (name "Net-(EPD_C6-Pad2)") (class "Default")
      (node (ref "EPD_C6") (pin "2") (pinfunction "2_2") (pintype "passive"))
      (node (ref "J1") (pin "18") (pinfunction "18_18") (pintype "bidirectional"))
    )
    (net (code "31") (name "Net-(EPD_C7-Pad2)") (class "Default")
      (node (ref "EPD_C7") (pin "2") (pinfunction "2_2") (pintype "passive"))
      (node (ref "J1") (pin "19") (pinfunction "19_19") (pintype "bidirectional"))
    )
    (net (code "32") (name "Net-(EPD_C8-Pad2)") (class "Default")
      (node (ref "EPD_C8") (pin "2") (pinfunction "2_2") (pintype "passive"))
      (node (ref "J1") (pin "20") (pinfunction "20_20") (pintype "bidirectional"))
    )
    (net (code "33") (name "Net-(EPD_C10-Pad2)") (class "Default")
      (node (ref "EPD_C10") (pin "2") (pinfunction "2_2") (pintype "passive"))
      (node (ref "J1") (pin "22") (pinfunction "22_22") (pintype "bidirectional"))
    )
    (net (code "34") (name "Net-(EPD_C12-Pad2)") (class "Default")
      (node (ref "EPD_C12") (pin "2") (pinfunction "2_2") (pintype "passive"))
      (node (ref "J1") (pin "24") (pinfunction "24_24") (pintype "bidirectional"))
    )
    (net (code "35") (name "Net-(IC1-TS{slash}MR)") (class "Default")
      (node (ref "IC1") (pin "D1") (pinfunction "TS/MR_D1") (pintype "bidirectional"))
      (node (ref "R9") (pin "2") (pinfunction "2_2") (pintype "bidirectional"))
    )
    (net (code "36") (name "Net-(IC2-REG)") (class "Default")
      (node (ref "C32") (pin "2") (pinfunction "2_2") (pintype "passive"))
      (node (ref "IC2") (pin "A2") (pinfunction "REG_A2") (pintype "bidirectional"))
    )
    (net (code "37") (name "Net-(IC3-SDO)") (class "Default")
      (node (ref "IC3") (pin "1") (pinfunction "SDO_1") (pintype "bidirectional"))
      (node (ref "R3") (pin "1") (pinfunction "1_1") (pintype "bidirectional"))
    )
    (net (code "38") (name "Net-(IC9-SCL)") (class "Default")
      (node (ref "IC9") (pin "D1") (pinfunction "SCL_D1") (pintype "bidirectional"))
      (node (ref "R4") (pin "1") (pinfunction "1_1") (pintype "bidirectional"))
    )
    (net (code "39") (name "Net-(IC9-SDA)") (class "Default")
      (node (ref "IC9") (pin "E1") (pinfunction "SDA_E1") (pintype "bidirectional"))
      (node (ref "R2") (pin "1") (pinfunction "1_1") (pintype "bidirectional"))
    )
    (net (code "40") (name "Net-(J4-CC1)") (class "Default")
      (node (ref "J4") (pin "A5") (pinfunction "CC1_A5") (pintype "bidirectional"))
      (node (ref "R1_USB") (pin "2") (pinfunction "2_2") (pintype "bidirectional"))
    )
    (net (code "41") (name "Net-(J4-CC2)") (class "Default")
      (node (ref "J4") (pin "B5") (pinfunction "CC2_B5") (pintype "bidirectional"))
      (node (ref "R2_USB") (pin "1") (pinfunction "1_1") (pintype "bidirectional"))
    )
    (net (code "42") (name "Net-(L2-Pad2)") (class "Default")
      (node (ref "L2") (pin "2") (pinfunction "2_2") (pintype "bidirectional"))
      (node (ref "L3") (pin "1") (pinfunction "1_1") (pintype "bidirectional"))
    )
    (net (code "43") (name "Net-(R1_EP_DR-Pad1)") (class "Default")
      (node (ref "R1_EP_DR") (pin "1") (pinfunction "1_1") (pintype "bidirectional"))
      (node (ref "R_TYPE_SEL") (pin "2") (pinfunction "2_2") (pintype "bidirectional"))
      (node (ref "SJ1") (pin "2") (pinfunction "2_2") (pintype "passive"))
    )
    (net (code "44") (name "Net-(U1-ANT)") (class "Default")
      (node (ref "C3") (pin "1") (pinfunction "1_1") (pintype "passive"))
      (node (ref "L1") (pin "1") (pinfunction "1_1") (pintype "passive"))
      (node (ref "U1") (pin "P$H23") (pinfunction "ANT_P$H23") (pintype "bidirectional"))
    )
    (net (code "45") (name "Net-(U1-DCC)") (class "Default")
      (node (ref "L2") (pin "1") (pinfunction "1_1") (pintype "bidirectional"))
      (node (ref "U1") (pin "P$B3") (pinfunction "DCC_P$B3") (pintype "output"))
    )
    (net (code "46") (name "Net-(U1-DEC2)") (class "Default")
      (node (ref "C13") (pin "1") (pinfunction "1_1") (pintype "passive"))
      (node (ref "U1") (pin "P$A18") (pinfunction "DEC2_P$A18") (pintype "bidirectional"))
    )
    (net (code "47") (name "Net-(U1-DEC3V3)") (class "Default")
      (node (ref "C20") (pin "1") (pinfunction "1_1") (pintype "passive"))
      (node (ref "U1") (pin "P$AC5") (pinfunction "DEC3V3_P$AC5") (pintype "bidirectional"))
    )
    (net (code "48") (name "Net-(U1-DEC5)") (class "Default")
      (node (ref "C9") (pin "1") (pinfunction "1_1") (pintype "passive"))
      (node (ref "U1") (pin "P$N24") (pinfunction "DEC5_P$N24") (pintype "bidirectional"))
    )
    (net (code "49") (name "Net-(U1-XC1)") (class "Default")
      (node (ref "C1") (pin "1") (pinfunction "1_1") (pintype "passive"))
      (node (ref "U1") (pin "P$B24") (pinfunction "XC1_P$B24") (pintype "input"))
      (node (ref "X1") (pin "1") (pinfunction "1_1") (pintype "passive"))
    )
    (net (code "50") (name "Net-(U1-XC2)") (class "Default")
      (node (ref "C2") (pin "1") (pinfunction "1_1") (pintype "passive"))
      (node (ref "U1") (pin "P$A23") (pinfunction "XC2_P$A23") (pintype "output"))
      (node (ref "X1") (pin "3") (pinfunction "3_3") (pintype "passive"))
    )
    (net (code "51") (name "OUT+") (class "Default")
      (node (ref "IC2") (pin "A3") (pinfunction "OUT+_A3") (pintype "bidirectional"))
      (node (ref "TP_OP") (pin "TP") (pinfunction "TP_TP") (pintype "input"))
    )
    (net (code "52") (name "OUT-") (class "Default")
      (node (ref "IC2") (pin "C3") (pinfunction "OUT-_C3") (pintype "bidirectional"))
      (node (ref "TP_ON") (pin "TP") (pinfunction "TP_TP") (pintype "input"))
    )
    (net (code "53") (name "P0.04") (class "Default")
      (node (ref "U1") (pin "P$J1") (pinfunction "P0.04/AIN2_P$J1") (pintype "bidirectional"))
    )
    (net (code "54") (name "P0.09") (class "Default")
      (node (ref "U1") (pin "P$L24") (pinfunction "P0.09/NFC1_P$L24") (pintype "bidirectional"))
    )
    (net (code "55") (name "P0.13") (class "Default")
      (node (ref "C29") (pin "2") (pinfunction "2_2") (pintype "passive"))
      (node (ref "R5") (pin "1") (pinfunction "1_1") (pintype "bidirectional"))
      (node (ref "SW_UP") (pin "2") (pinfunction "2_2") (pintype "passive"))
      (node (ref "U1") (pin "P$AD8") (pinfunction "P0.13_P$AD8") (pintype "bidirectional"))
    )
    (net (code "56") (name "P0.14") (class "Default")
      (node (ref "C30") (pin "2") (pinfunction "2_2") (pintype "passive"))
      (node (ref "R8") (pin "1") (pinfunction "1_1") (pintype "bidirectional"))
      (node (ref "SW_ENT") (pin "2") (pinfunction "2_2") (pintype "passive"))
      (node (ref "U1") (pin "P$AC9") (pinfunction "P0.14_P$AC9") (pintype "bidirectional"))
    )
    (net (code "57") (name "P0.19") (class "Default")
      (node (ref "U1") (pin "P$AC15") (pinfunction "P0.19_P$AC15") (pintype "bidirectional"))
    )
    (net (code "58") (name "P0.20") (class "Default")
      (node (ref "U1") (pin "P$AD16") (pinfunction "P0.20_P$AD16") (pintype "bidirectional"))
    )
    (net (code "59") (name "P0.21") (class "Default")
      (node (ref "U1") (pin "P$AC17") (pinfunction "P0.21_P$AC17") (pintype "bidirectional"))
    )
    (net (code "60") (name "P0.22") (class "Default")
      (node (ref "U1") (pin "P$AD18") (pinfunction "P0.22_P$AD18") (pintype "bidirectional"))
    )
    (net (code "61") (name "P0.23") (class "Default")
      (node (ref "U1") (pin "P$AC19") (pinfunction "P0.23_P$AC19") (pintype "bidirectional"))
    )
    (net (code "62") (name "P0.24") (class "Default")
      (node (ref "U1") (pin "P$AD20") (pinfunction "P0.24_P$AD20") (pintype "bidirectional"))
    )
    (net (code "63") (name "P0.25") (class "Default")
      (node (ref "U1") (pin "P$AC21") (pinfunction "P0.25_P$AC21") (pintype "bidirectional"))
    )
    (net (code "64") (name "P0.26") (class "Default")
      (node (ref "U1") (pin "P$G1") (pinfunction "P0.26_P$G1") (pintype "bidirectional"))
    )
    (net (code "65") (name "P0.27") (class "Default")
      (node (ref "U1") (pin "P$H2") (pinfunction "P0.27_P$H2") (pintype "bidirectional"))
    )
    (net (code "66") (name "P0.28") (class "Default")
      (node (ref "U1") (pin "P$B11") (pinfunction "P0.28/AIN4_P$B11") (pintype "bidirectional"))
    )
    (net (code "67") (name "P0.29") (class "Default")
      (node (ref "U1") (pin "P$A10") (pinfunction "P0.29/AIN5_P$A10") (pintype "bidirectional"))
    )
    (net (code "68") (name "P0.30") (class "Default")
      (node (ref "U1") (pin "P$B9") (pinfunction "P0.30/AIN6_P$B9") (pintype "bidirectional"))
    )
    (net (code "69") (name "P0.31") (class "Default")
      (node (ref "U1") (pin "P$A8") (pinfunction "P0.31/AIN7_P$A8") (pintype "bidirectional"))
    )
    (net (code "70") (name "P1.01") (class "Default")
      (node (ref "Q2") (pin "1") (pinfunction "G_1") (pintype "bidirectional"))
      (node (ref "R_PWR_EPD") (pin "1") (pinfunction "1_1") (pintype "bidirectional"))
      (node (ref "U1") (pin "P$Y23") (pinfunction "P1.01_P$Y23") (pintype "bidirectional"))
    )
    (net (code "71") (name "P1.02") (class "Default")
      (node (ref "C31") (pin "2") (pinfunction "2_2") (pintype "passive"))
      (node (ref "R7") (pin "1") (pinfunction "1_1") (pintype "bidirectional"))
      (node (ref "SW_DN") (pin "2") (pinfunction "2_2") (pintype "passive"))
      (node (ref "U1") (pin "P$W24") (pinfunction "P1.02_P$W24") (pintype "bidirectional"))
    )
    (net (code "72") (name "P1.03") (class "Default")
      (node (ref "U1") (pin "P$V23") (pinfunction "P1.03_P$V23") (pintype "bidirectional"))
    )
    (net (code "73") (name "P1.04") (class "Default")
      (node (ref "U1") (pin "P$U24") (pinfunction "P1.04_P$U24") (pintype "bidirectional"))
    )
    (net (code "74") (name "P1.05") (class "Default")
      (node (ref "U1") (pin "P$T23") (pinfunction "P1.05_P$T23") (pintype "bidirectional"))
    )
    (net (code "75") (name "P1.06") (class "Default")
      (node (ref "U1") (pin "P$R24") (pinfunction "P1.06_P$R24") (pintype "bidirectional"))
    )
    (net (code "76") (name "P1.07") (class "Default")
      (node (ref "U1") (pin "P$P23") (pinfunction "P1.07_P$P23") (pintype "bidirectional"))
    )
    (net (code "77") (name "P1.09") (class "Default")
      (node (ref "U1") (pin "P$R1") (pinfunction "P1.09_P$R1") (pintype "bidirectional"))
    )
    (net (code "78") (name "P1.10") (class "Default")
      (node (ref "U1") (pin "P$A20") (pinfunction "P1.10_P$A20") (pintype "bidirectional"))
    )
    (net (code "79") (name "P1.11") (class "Default")
      (node (ref "U1") (pin "P$B19") (pinfunction "P1.11_P$B19") (pintype "bidirectional"))
    )
    (net (code "80") (name "P1.12") (class "Default")
      (node (ref "U1") (pin "P$B17") (pinfunction "P1.12_P$B17") (pintype "bidirectional"))
    )
    (net (code "81") (name "P1.13") (class "Default")
      (node (ref "U1") (pin "P$A16") (pinfunction "P1.13_P$A16") (pintype "bidirectional"))
    )
    (net (code "82") (name "P1.14") (class "Default")
      (node (ref "U1") (pin "P$B15") (pinfunction "P1.14_P$B15") (pintype "bidirectional"))
    )
    (net (code "83") (name "P1.15") (class "Default")
      (node (ref "U1") (pin "P$A14") (pinfunction "P1.15_P$A14") (pintype "bidirectional"))
    )
    (net (code "84") (name "PMIC_INT") (class "Default")
      (node (ref "IC1") (pin "A1") (pinfunction "~{INT}_A1") (pintype "bidirectional"))
      (node (ref "U1") (pin "P$T2") (pinfunction "P0.11_P$T2") (pintype "bidirectional"))
    )
    (net (code "85") (name "PREVGH") (class "Default")
      (node (ref "D5") (pin "1") (pinfunction "K_1") (pintype "bidirectional"))
      (node (ref "EPD_C9") (pin "2") (pinfunction "2_2") (pintype "passive"))
      (node (ref "J1") (pin "21") (pinfunction "21_21") (pintype "bidirectional"))
    )
    (net (code "86") (name "PREVGL") (class "Default")
      (node (ref "D2") (pin "2") (pinfunction "A_2") (pintype "bidirectional"))
      (node (ref "EPD_C11") (pin "2") (pinfunction "2_2") (pintype "passive"))
      (node (ref "J1") (pin "23") (pinfunction "23_23") (pintype "bidirectional"))
    )
    (net (code "87") (name "RESE") (class "Default")
      (node (ref "J1") (pin "3") (pinfunction "3_3") (pintype "bidirectional"))
      (node (ref "Q1") (pin "2") (pinfunction "S_2") (pintype "bidirectional"))
      (node (ref "R1_EP_DR") (pin "2") (pinfunction "2_2") (pintype "bidirectional"))
    )
    (net (code "88") (name "RESET") (class "Default")
      (node (ref "J2") (pin "6") (pinfunction "6_6") (pintype "bidirectional"))
      (node (ref "TP_RESET") (pin "TP") (pinfunction "TP_TP") (pintype "input"))
      (node (ref "U1") (pin "P$AC13") (pinfunction "P0.18/RESET_P$AC13") (pintype "bidirectional"))
    )
    (net (code "89") (name "SCK") (class "Default")
      (node (ref "J1") (pin "13") (pinfunction "13_13") (pintype "bidirectional"))
      (node (ref "U1") (pin "P$A12") (pinfunction "P0.02/AIN0_P$A12") (pintype "bidirectional"))
    )
    (net (code "90") (name "SCL") (class "Default")
      (node (ref "IC1") (pin "B1") (pinfunction "SCL_B1") (pintype "bidirectional"))
      (node (ref "IC2") (pin "C1") (pinfunction "SCL_C1") (pintype "bidirectional"))
      (node (ref "IC3") (pin "12") (pinfunction "SCX_12") (pintype "bidirectional"))
      (node (ref "R17") (pin "2") (pinfunction "2_2") (pintype "bidirectional"))
      (node (ref "R4") (pin "2") (pinfunction "2_2") (pintype "bidirectional"))
      (node (ref "TP_SCL") (pin "TP") (pinfunction "TP_TP") (pintype "input"))
      (node (ref "U1") (pin "P$M2") (pinfunction "P0.07_P$M2") (pintype "bidirectional"))
      (node (ref "U3") (pin "7") (pinfunction "SCL_7") (pintype "input"))
    )
    (net (code "91") (name "SDA") (class "Default")
      (node (ref "IC1") (pin "C1") (pinfunction "SDA_C1") (pintype "bidirectional"))
      (node (ref "IC2") (pin "B2") (pinfunction "SDA_B2") (pintype "bidirectional"))
      (node (ref "IC3") (pin "2") (pinfunction "SDX_2") (pintype "bidirectional"))
      (node (ref "R18") (pin "2") (pinfunction "2_2") (pintype "bidirectional"))
      (node (ref "R2") (pin "2") (pinfunction "2_2") (pintype "bidirectional"))
      (node (ref "TP_SDA") (pin "TP") (pinfunction "TP_TP") (pintype "input"))
      (node (ref "U1") (pin "P$L1") (pinfunction "P0.06_P$L1") (pintype "bidirectional"))
      (node (ref "U3") (pin "8") (pinfunction "SDA_8") (pintype "bidirectional"))
    )
    (net (code "92") (name "SWDCLK") (class "Default")
      (node (ref "J2") (pin "4") (pinfunction "4_4") (pintype "bidirectional"))
      (node (ref "TP_SWDCLK") (pin "TP") (pinfunction "TP_TP") (pintype "input"))
      (node (ref "U1") (pin "P$AA24") (pinfunction "SWDCLK_P$AA24") (pintype "input"))
    )
    (net (code "93") (name "SWDIO") (class "Default")
      (node (ref "J2") (pin "2") (pinfunction "2_2") (pintype "bidirectional"))
      (node (ref "TP_SWDIO") (pin "TP") (pinfunction "TP_TP") (pintype "input"))
      (node (ref "U1") (pin "P$AC24") (pinfunction "SWDIO_P$AC24") (pintype "bidirectional"))
    )
    (net (code "94") (name "SWO") (class "Default")
      (node (ref "TP_SWO") (pin "TP") (pinfunction "TP_TP") (pintype "input"))
      (node (ref "U1") (pin "P$AD22") (pinfunction "P1.00_P$AD22") (pintype "bidirectional"))
    )
    (net (code "95") (name "VBAT") (class "Default")
      (node (ref "C27") (pin "2") (pinfunction "2_2") (pintype "passive"))
      (node (ref "C37") (pin "2") (pinfunction "2_2") (pintype "passive"))
      (node (ref "IC1") (pin "C2") (pinfunction "BAT_C2") (pintype "bidirectional"))
      (node (ref "TP_VBAT") (pin "TP") (pinfunction "TP_TP") (pintype "input"))
      (node (ref "U3") (pin "2") (pinfunction "CELL_2") (pintype "power_in"))
      (node (ref "U3") (pin "3") (pinfunction "VDD_3") (pintype "power_in"))
    )
    (net (code "96") (name "VBUS") (class "Default")
      (node (ref "C21") (pin "1") (pinfunction "1_1") (pintype "passive"))
      (node (ref "C38") (pin "2") (pinfunction "2_2") (pintype "passive"))
      (node (ref "C42") (pin "1") (pinfunction "1_1") (pintype "passive"))
      (node (ref "C43") (pin "1") (pinfunction "1_1") (pintype "passive"))
      (node (ref "D3") (pin "5") (pinfunction "VBUS_5") (pintype "bidirectional"))
      (node (ref "IC1") (pin "A2") (pinfunction "IN_A2") (pintype "bidirectional"))
      (node (ref "J4") (pin "A4_B9") (pinfunction "VBUS_A4_B9") (pintype "power_in"))
      (node (ref "J4") (pin "A9_B4") (pinfunction "VBUS_A9_B4") (pintype "power_in"))
      (node (ref "U1") (pin "P$AD2") (pinfunction "VBUS_P$AD2") (pintype "power_in"))
    )
    (net (code "97") (name "VREG") (class "Default")
      (node (ref "C23") (pin "2") (pinfunction "2_2") (pintype "passive"))
      (node (ref "C24") (pin "2") (pinfunction "2_2") (pintype "passive"))
      (node (ref "C39") (pin "1") (pinfunction "1_1") (pintype "passive"))
      (node (ref "IC1") (pin "B2") (pinfunction "SYS_B2") (pintype "bidirectional"))
      (node (ref "IC9") (pin "A1") (pinfunction "EN_A1") (pintype "bidirectional"))
      (node (ref "IC9") (pin "A2") (pinfunction "VIN_1_A2") (pintype "bidirectional"))
      (node (ref "IC9") (pin "A3") (pinfunction "VIN_2_A3") (pintype "bidirectional"))
      (node (ref "TP_VREG") (pin "TP") (pinfunction "TP_TP") (pintype "input"))
    )
    (net (code "98") (name "unconnected-(ANT1-NC-Pad2)") (class "Default")
      (node (ref "ANT1") (pin "2") (pinfunction "NC_2") (pintype "no_connect"))
    )
    (net (code "99") (name "unconnected-(IC3-ASCL-Pad11)") (class "Default")
      (node (ref "IC3") (pin "11") (pinfunction "ASCL_11") (pintype "bidirectional"))
    )
    (net (code "100") (name "unconnected-(IC3-ASDA-Pad4)") (class "Default")
      (node (ref "IC3") (pin "4") (pinfunction "ASDA_4") (pintype "bidirectional"))
    )
    (net (code "101") (name "unconnected-(J1-Pad1)") (class "Default")
      (node (ref "J1") (pin "1") (pinfunction "1_1") (pintype "bidirectional"))
    )
    (net (code "102") (name "unconnected-(J1-Pad6)") (class "Default")
      (node (ref "J1") (pin "6") (pinfunction "6_6") (pintype "bidirectional"))
    )
    (net (code "103") (name "unconnected-(J1-Pad7)") (class "Default")
      (node (ref "J1") (pin "7") (pinfunction "7_7") (pintype "bidirectional"))
    )
    (net (code "104") (name "unconnected-(J4-SBU1-PadA8)") (class "Default")
      (node (ref "J4") (pin "A8") (pinfunction "SBU1_A8") (pintype "bidirectional"))
    )
    (net (code "105") (name "unconnected-(J4-SBU2-PadB8)") (class "Default")
      (node (ref "J4") (pin "B8") (pinfunction "SBU2_B8") (pintype "bidirectional"))
    )
    (net (code "106") (name "unconnected-(U1-DCCH-PadP$AB2)") (class "Default")
      (node (ref "U1") (pin "P$AB2") (pinfunction "DCCH_P$AB2") (pintype "bidirectional"))
    )
  )
)
